# ArduinoInterface_v3_1.net
KiCad netlist of a schematic drawn in EAGLE
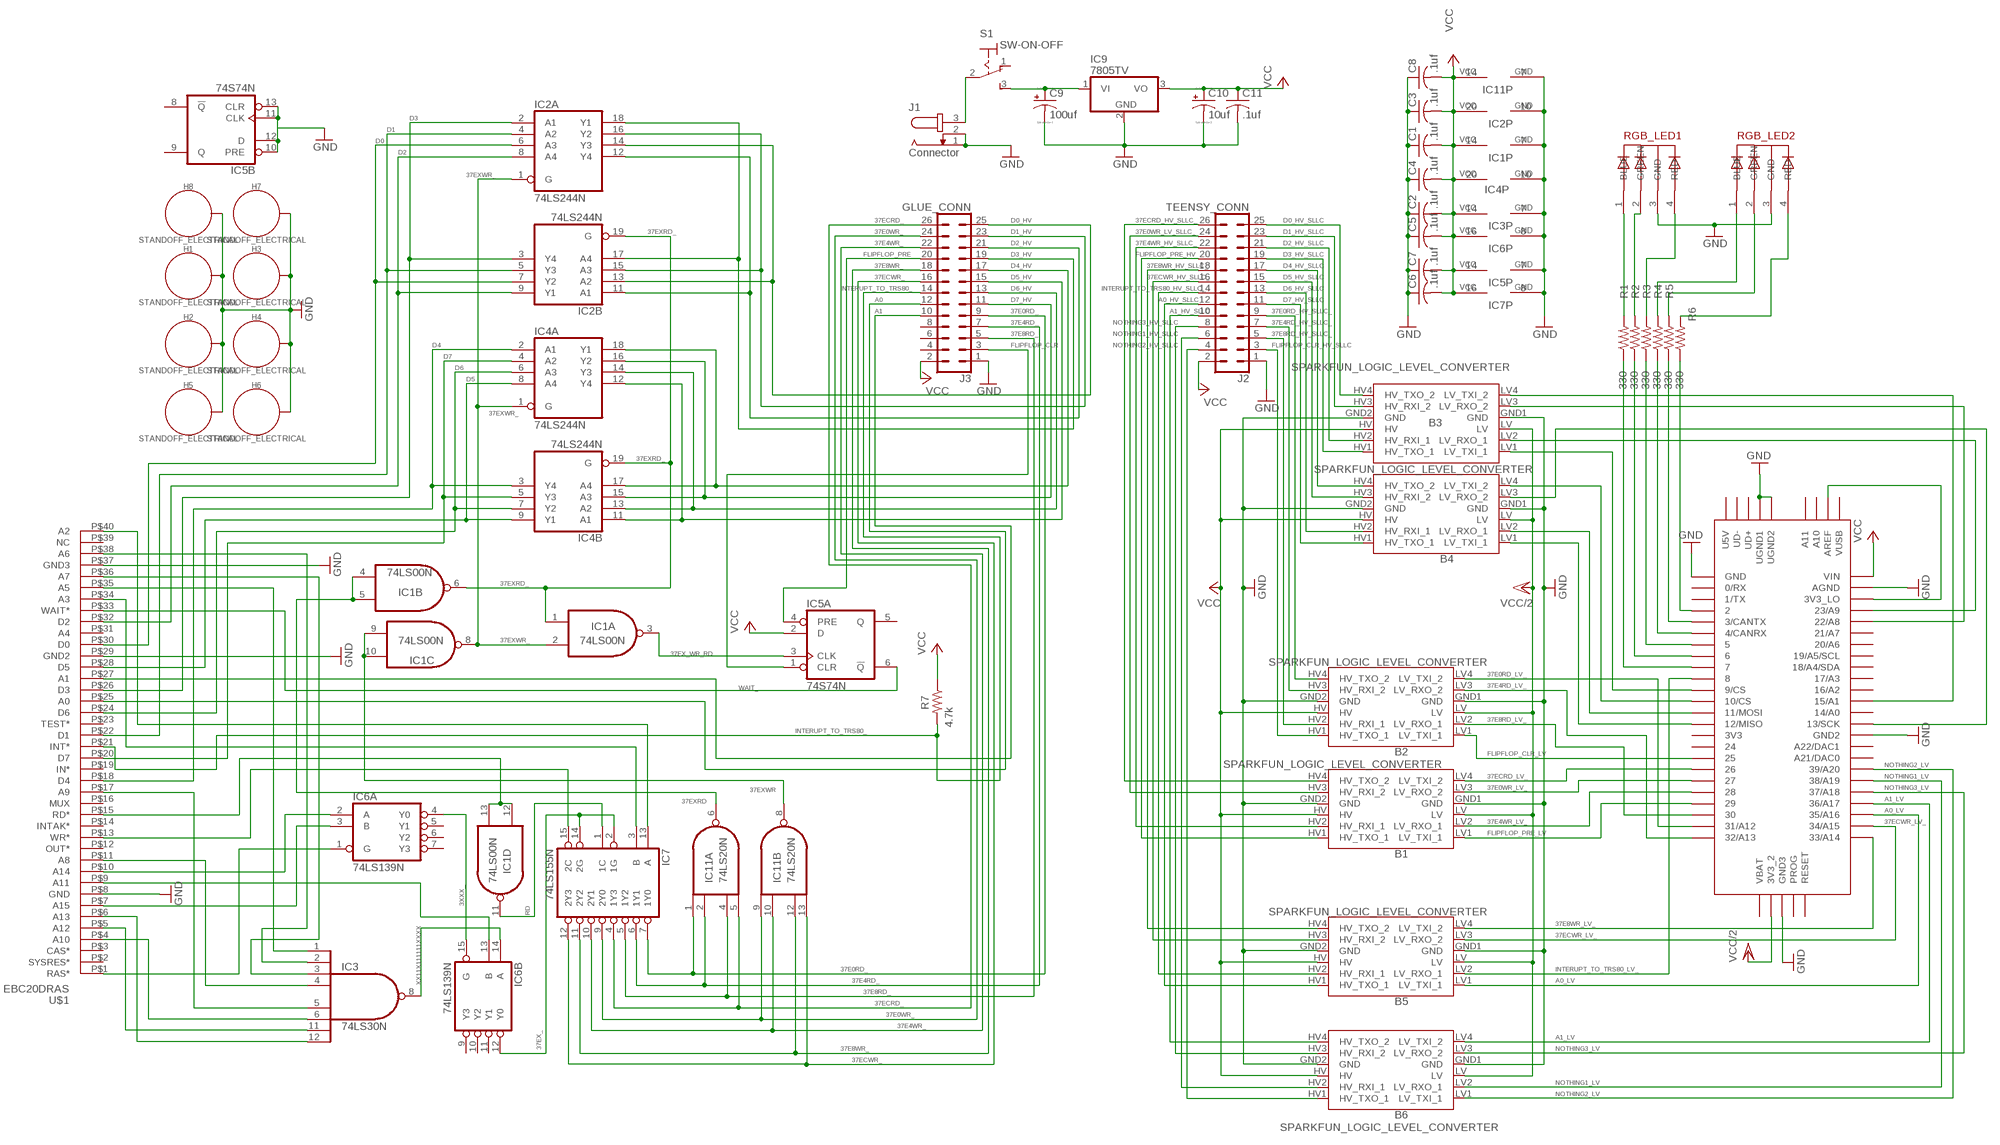
[diagram p0: schematic, sheet 1]

(export (version "E")
  (design (tool "Eeschema 10.0.6"))
  (components
    (comp (ref "B1")
      (value "SPARKFUN_LOGIC_LEVEL_CONVERTER")
      (footprint "eagle-import:SPARKFUN_LOGIC_LEVEL_CONVERTER")
      (libsource (lib "eagle-import") (part "SPARKFUN_LOGIC_LEVEL_CONVERTER"))
    )
    (comp (ref "B2")
      (value "SPARKFUN_LOGIC_LEVEL_CONVERTER")
      (footprint "eagle-import:SPARKFUN_LOGIC_LEVEL_CONVERTER")
      (libsource (lib "eagle-import") (part "SPARKFUN_LOGIC_LEVEL_CONVERTER"))
    )
    (comp (ref "B3")
      (value "SPARKFUN_LOGIC_LEVEL_CONVERTER")
      (footprint "eagle-import:SPARKFUN_LOGIC_LEVEL_CONVERTER")
      (libsource (lib "eagle-import") (part "SPARKFUN_LOGIC_LEVEL_CONVERTER"))
    )
    (comp (ref "B4")
      (value "SPARKFUN_LOGIC_LEVEL_CONVERTER")
      (footprint "eagle-import:SPARKFUN_LOGIC_LEVEL_CONVERTER")
      (libsource (lib "eagle-import") (part "SPARKFUN_LOGIC_LEVEL_CONVERTER"))
    )
    (comp (ref "B5")
      (value "SPARKFUN_LOGIC_LEVEL_CONVERTER")
      (footprint "eagle-import:SPARKFUN_LOGIC_LEVEL_CONVERTER")
      (libsource (lib "eagle-import") (part "SPARKFUN_LOGIC_LEVEL_CONVERTER"))
    )
    (comp (ref "B6")
      (value "SPARKFUN_LOGIC_LEVEL_CONVERTER")
      (footprint "eagle-import:SPARKFUN_LOGIC_LEVEL_CONVERTER")
      (libsource (lib "eagle-import") (part "SPARKFUN_LOGIC_LEVEL_CONVERTER"))
    )
    (comp (ref "C1")
      (value ".1uf")
      (footprint "eagle-import:C025-025X050")
      (libsource (lib "eagle-import") (part "C-US025-025X050"))
    )
    (comp (ref "C2")
      (value ".1uf")
      (footprint "eagle-import:C025-025X050")
      (libsource (lib "eagle-import") (part "C-US025-025X050"))
    )
    (comp (ref "C3")
      (value ".1uf")
      (footprint "eagle-import:C025-025X050")
      (libsource (lib "eagle-import") (part "C-US025-025X050"))
    )
    (comp (ref "C4")
      (value ".1uf")
      (footprint "eagle-import:C025-025X050")
      (libsource (lib "eagle-import") (part "C-US025-025X050"))
    )
    (comp (ref "C5")
      (value ".1uf")
      (footprint "eagle-import:C025-025X050")
      (libsource (lib "eagle-import") (part "C-US025-025X050"))
    )
    (comp (ref "C6")
      (value ".1uf")
      (footprint "eagle-import:C025-025X050")
      (libsource (lib "eagle-import") (part "C-US025-025X050"))
    )
    (comp (ref "C7")
      (value ".1uf")
      (footprint "eagle-import:C025-025X050")
      (libsource (lib "eagle-import") (part "C-US025-025X050"))
    )
    (comp (ref "C8")
      (value ".1uf")
      (footprint "eagle-import:C025-025X050")
      (libsource (lib "eagle-import") (part "C-US025-025X050"))
    )
    (comp (ref "C9")
      (value "100uf")
      (footprint "eagle-import:E5-6")
      (libsource (lib "eagle-import") (part "CPOL-USE5-6"))
    )
    (comp (ref "C10")
      (value "10uf")
      (footprint "eagle-import:E5-6")
      (libsource (lib "eagle-import") (part "CPOL-USE5-6"))
    )
    (comp (ref "C11")
      (value ".1uf")
      (footprint "eagle-import:C025-025X050")
      (libsource (lib "eagle-import") (part "C-US025-025X050"))
    )
    (comp (ref "H1")
      (value "STANDOFF_ELECTRICAL")
      (footprint "eagle-import:STANDOFF-ELECTRICAL")
      (libsource (lib "eagle-import") (part "STANDOFF_ELECTRICAL"))
    )
    (comp (ref "H2")
      (value "STANDOFF_ELECTRICAL")
      (footprint "eagle-import:STANDOFF-ELECTRICAL")
      (libsource (lib "eagle-import") (part "STANDOFF_ELECTRICAL"))
    )
    (comp (ref "H3")
      (value "STANDOFF_ELECTRICAL")
      (footprint "eagle-import:STANDOFF-ELECTRICAL")
      (libsource (lib "eagle-import") (part "STANDOFF_ELECTRICAL"))
    )
    (comp (ref "H4")
      (value "STANDOFF_ELECTRICAL")
      (footprint "eagle-import:STANDOFF-ELECTRICAL")
      (libsource (lib "eagle-import") (part "STANDOFF_ELECTRICAL"))
    )
    (comp (ref "H5")
      (value "STANDOFF_ELECTRICAL")
      (footprint "eagle-import:STANDOFF-ELECTRICAL")
      (libsource (lib "eagle-import") (part "STANDOFF_ELECTRICAL"))
    )
    (comp (ref "H6")
      (value "STANDOFF_ELECTRICAL")
      (footprint "eagle-import:STANDOFF-ELECTRICAL")
      (libsource (lib "eagle-import") (part "STANDOFF_ELECTRICAL"))
    )
    (comp (ref "H7")
      (value "STANDOFF_ELECTRICAL")
      (footprint "eagle-import:STANDOFF-ELECTRICAL")
      (libsource (lib "eagle-import") (part "STANDOFF_ELECTRICAL"))
    )
    (comp (ref "H8")
      (value "STANDOFF_ELECTRICAL")
      (footprint "eagle-import:STANDOFF-ELECTRICAL")
      (libsource (lib "eagle-import") (part "STANDOFF_ELECTRICAL"))
    )
    (comp (ref "IC1")
      (value "74LS00N")
      (footprint "eagle-import:DIL14")
      (libsource (lib "eagle-import") (part "7400NLS"))
    )
    (comp (ref "IC2")
      (value "74LS244N")
      (footprint "eagle-import:DIL20")
      (libsource (lib "eagle-import") (part "74244NLS"))
    )
    (comp (ref "IC3")
      (value "74LS30N")
      (footprint "eagle-import:DIL14")
      (libsource (lib "eagle-import") (part "7430NLS"))
    )
    (comp (ref "IC4")
      (value "74LS244N")
      (footprint "eagle-import:DIL20")
      (libsource (lib "eagle-import") (part "74244NLS"))
    )
    (comp (ref "IC5")
      (value "74S74N")
      (footprint "eagle-import:DIL14")
      (libsource (lib "eagle-import") (part "7474NS"))
    )
    (comp (ref "IC6")
      (value "74LS139N")
      (footprint "eagle-import:DIL16")
      (libsource (lib "eagle-import") (part "74139NLS"))
    )
    (comp (ref "IC7")
      (value "74LS155N")
      (footprint "eagle-import:DIL16")
      (libsource (lib "eagle-import") (part "74155NLS"))
    )
    (comp (ref "IC9")
      (value "7805TV")
      (footprint "eagle-import:TO220V")
      (libsource (lib "eagle-import") (part "78TV05"))
    )
    (comp (ref "IC11")
      (value "74LS20N")
      (footprint "eagle-import:DIL14")
      (libsource (lib "eagle-import") (part "7420NLS"))
    )
    (comp (ref "J1")
      (value "Connector")
      (footprint "eagle-import:SPC4077")
      (libsource (lib "eagle-import") (part "JACK-PLUG0"))
    )
    (comp (ref "J2")
      (value "TEENSY_CONN")
      (footprint "eagle-import:2X13")
      (libsource (lib "eagle-import") (part "CONN_13X22X13"))
    )
    (comp (ref "J3")
      (value "GLUE_CONN")
      (footprint "eagle-import:2X13")
      (libsource (lib "eagle-import") (part "CONN_13X22X13"))
    )
    (comp (ref "R1")
      (value "330")
      (footprint "eagle-import:0204V")
      (libsource (lib "eagle-import") (part "R-US_0204/2V"))
    )
    (comp (ref "R2")
      (value "330")
      (footprint "eagle-import:0204V")
      (libsource (lib "eagle-import") (part "R-US_0204/2V"))
    )
    (comp (ref "R3")
      (value "330")
      (footprint "eagle-import:0204V")
      (libsource (lib "eagle-import") (part "R-US_0204/2V"))
    )
    (comp (ref "R4")
      (value "330")
      (footprint "eagle-import:0204V")
      (libsource (lib "eagle-import") (part "R-US_0204/2V"))
    )
    (comp (ref "R5")
      (value "330")
      (footprint "eagle-import:0204V")
      (libsource (lib "eagle-import") (part "R-US_0204/2V"))
    )
    (comp (ref "R6")
      (value "330")
      (footprint "eagle-import:0204V")
      (libsource (lib "eagle-import") (part "R-US_0204/2V"))
    )
    (comp (ref "R7")
      (value "4.7k")
      (footprint "eagle-import:0204V")
      (libsource (lib "eagle-import") (part "R-US_0204/2V"))
    )
    (comp (ref "RGB_LED1")
      (value "5MMRGBLED")
      (footprint "eagle-import:LED5MMRGB")
      (libsource (lib "eagle-import") (part "5MMRGBLED"))
    )
    (comp (ref "RGB_LED2")
      (value "5MMRGBLED")
      (footprint "eagle-import:LED5MMRGB")
      (libsource (lib "eagle-import") (part "5MMRGBLED"))
    )
    (comp (ref "S1")
      (value "SW-ON-OFF")
      (footprint "eagle-import:M9040P")
      (libsource (lib "eagle-import") (part "M9040P"))
    )
    (comp (ref "U$1")
      (value "EBC20DRAS")
      (footprint "eagle-import:EBC20DRAS")
      (libsource (lib "eagle-import") (part "EBC20DRAS"))
    )
    (comp (ref "U$2")
      (value "TEENSY_3.5/3.6")
      (footprint "eagle-import:TEENSY_3.5_3.6")
      (libsource (lib "eagle-import") (part "TEENSY_3.5/3.6"))
    )
  )
  (nets
    (net (code "1") (name "/3XXX_") (class "Default")
      (node (ref "IC6") (pin "15") (pinfunction "G_15") (pintype "input"))
      (node (ref "IC6") (pin "4") (pinfunction "Y0_4") (pintype "output"))
    )
    (net (code "2") (name "/37E0RD_") (class "Default")
      (node (ref "IC11") (pin "1") (pinfunction "I0_1") (pintype "input"))
      (node (ref "IC7") (pin "7") (pinfunction "1Y0_7") (pintype "output"))
      (node (ref "J3") (pin "9") (pinfunction "9_9") (pintype "passive"))
    )
    (net (code "3") (name "/37E0RD_HV_SLLC_") (class "Default")
      (node (ref "B2") (pin "HV4") (pinfunction "HV_TXO_2_HV4") (pintype "bidirectional"))
      (node (ref "J2") (pin "9") (pinfunction "9_9") (pintype "passive"))
    )
    (net (code "4") (name "/37E0RD_LV_") (class "Default")
      (node (ref "B2") (pin "LV4") (pinfunction "LV_TXI_2_LV4") (pintype "bidirectional"))
      (node (ref "U$2") (pin "31/A12") (pinfunction "31/A12_31/A12") (pintype "bidirectional"))
    )
    (net (code "5") (name "/37E0WR_") (class "Default")
      (node (ref "IC11") (pin "9") (pinfunction "I0_9") (pintype "input"))
      (node (ref "IC7") (pin "9") (pinfunction "2Y0_9") (pintype "output"))
      (node (ref "J3") (pin "24") (pinfunction "24_24") (pintype "passive"))
    )
    (net (code "6") (name "/37E0WR_LV_") (class "Default")
      (node (ref "B1") (pin "LV3") (pinfunction "LV_RXO_2_LV3") (pintype "bidirectional"))
      (node (ref "U$2") (pin "27") (pinfunction "27_27") (pintype "bidirectional"))
    )
    (net (code "7") (name "/37E0WR_LV_SLLC_") (class "Default")
      (node (ref "B1") (pin "HV3") (pinfunction "HV_RXI_2_HV3") (pintype "bidirectional"))
      (node (ref "J2") (pin "24") (pinfunction "24_24") (pintype "passive"))
    )
    (net (code "8") (name "/37E4RD_") (class "Default")
      (node (ref "IC11") (pin "2") (pinfunction "I1_2") (pintype "input"))
      (node (ref "IC7") (pin "6") (pinfunction "1Y1_6") (pintype "output"))
      (node (ref "J3") (pin "7") (pinfunction "7_7") (pintype "passive"))
    )
    (net (code "9") (name "/37E4RD_HV_SLLC_") (class "Default")
      (node (ref "B2") (pin "HV3") (pinfunction "HV_RXI_2_HV3") (pintype "bidirectional"))
      (node (ref "J2") (pin "7") (pinfunction "7_7") (pintype "passive"))
    )
    (net (code "10") (name "/37E4RD_LV_") (class "Default")
      (node (ref "B2") (pin "LV3") (pinfunction "LV_RXO_2_LV3") (pintype "bidirectional"))
      (node (ref "U$2") (pin "32/A13") (pinfunction "32/A13_32/A13") (pintype "bidirectional"))
    )
    (net (code "11") (name "/37E4WR_") (class "Default")
      (node (ref "IC11") (pin "10") (pinfunction "I1_10") (pintype "input"))
      (node (ref "IC7") (pin "10") (pinfunction "2Y1_10") (pintype "output"))
      (node (ref "J3") (pin "22") (pinfunction "22_22") (pintype "passive"))
    )
    (net (code "12") (name "/37E4WR_HV_SLLC_") (class "Default")
      (node (ref "B1") (pin "HV2") (pinfunction "HV_RXI_1_HV2") (pintype "bidirectional"))
      (node (ref "J2") (pin "22") (pinfunction "22_22") (pintype "passive"))
    )
    (net (code "13") (name "/37E4WR_LV_") (class "Default")
      (node (ref "B1") (pin "LV2") (pinfunction "LV_RXO_1_LV2") (pintype "bidirectional"))
      (node (ref "U$2") (pin "28") (pinfunction "28_28") (pintype "bidirectional"))
    )
    (net (code "14") (name "/37E8RD_") (class "Default")
      (node (ref "IC11") (pin "4") (pinfunction "I2_4") (pintype "input"))
      (node (ref "IC7") (pin "5") (pinfunction "1Y2_5") (pintype "output"))
      (node (ref "J3") (pin "5") (pinfunction "5_5") (pintype "passive"))
    )
    (net (code "15") (name "/37E8RD_HV_SLLC_") (class "Default")
      (node (ref "B2") (pin "HV2") (pinfunction "HV_RXI_1_HV2") (pintype "bidirectional"))
      (node (ref "J2") (pin "5") (pinfunction "5_5") (pintype "passive"))
    )
    (net (code "16") (name "/37E8RD_LV_") (class "Default")
      (node (ref "B2") (pin "LV2") (pinfunction "LV_RXO_1_LV2") (pintype "bidirectional"))
      (node (ref "U$2") (pin "30") (pinfunction "30_30") (pintype "bidirectional"))
    )
    (net (code "17") (name "/37E8WR_") (class "Default")
      (node (ref "IC11") (pin "12") (pinfunction "I2_12") (pintype "input"))
      (node (ref "IC7") (pin "11") (pinfunction "2Y2_11") (pintype "output"))
      (node (ref "J3") (pin "18") (pinfunction "18_18") (pintype "passive"))
    )
    (net (code "18") (name "/37E8WR_HV_SLLC_") (class "Default")
      (node (ref "B5") (pin "HV4") (pinfunction "HV_TXO_2_HV4") (pintype "bidirectional"))
      (node (ref "J2") (pin "18") (pinfunction "18_18") (pintype "passive"))
    )
    (net (code "19") (name "/37E8WR_LV_") (class "Default")
      (node (ref "B5") (pin "LV4") (pinfunction "LV_TXI_2_LV4") (pintype "bidirectional"))
      (node (ref "U$2") (pin "33/A14") (pinfunction "33/A14_33/A14") (pintype "bidirectional"))
    )
    (net (code "20") (name "/37ECRD_") (class "Default")
      (node (ref "IC11") (pin "5") (pinfunction "I3_5") (pintype "input"))
      (node (ref "IC7") (pin "4") (pinfunction "1Y3_4") (pintype "output"))
      (node (ref "J3") (pin "26") (pinfunction "26_26") (pintype "passive"))
    )
    (net (code "21") (name "/37ECRD_HV_SLLC_") (class "Default")
      (node (ref "B1") (pin "HV4") (pinfunction "HV_TXO_2_HV4") (pintype "bidirectional"))
      (node (ref "J2") (pin "26") (pinfunction "26_26") (pintype "passive"))
    )
    (net (code "22") (name "/37ECRD_LV_") (class "Default")
      (node (ref "B1") (pin "LV4") (pinfunction "LV_TXI_2_LV4") (pintype "bidirectional"))
      (node (ref "U$2") (pin "26") (pinfunction "26_26") (pintype "bidirectional"))
    )
    (net (code "23") (name "/37ECWR_") (class "Default")
      (node (ref "IC11") (pin "13") (pinfunction "I3_13") (pintype "input"))
      (node (ref "IC7") (pin "12") (pinfunction "2Y3_12") (pintype "output"))
      (node (ref "J3") (pin "16") (pinfunction "16_16") (pintype "passive"))
    )
    (net (code "24") (name "/37ECWR_HV_SLLC_") (class "Default")
      (node (ref "B5") (pin "HV3") (pinfunction "HV_RXI_2_HV3") (pintype "bidirectional"))
      (node (ref "J2") (pin "16") (pinfunction "16_16") (pintype "passive"))
    )
    (net (code "25") (name "/37ECWR_LV_") (class "Default")
      (node (ref "B5") (pin "LV3") (pinfunction "LV_RXO_2_LV3") (pintype "bidirectional"))
      (node (ref "U$2") (pin "34/A15") (pinfunction "34/A15_34/A15") (pintype "bidirectional"))
    )
    (net (code "26") (name "/37EXRD") (class "Default")
      (node (ref "IC1") (pin "4") (pinfunction "I0_4") (pintype "input"))
      (node (ref "IC1") (pin "5") (pinfunction "I1_5") (pintype "input"))
      (node (ref "IC11") (pin "6") (pinfunction "O_6") (pintype "output"))
    )
    (net (code "27") (name "/37EXRD_") (class "Default")
      (node (ref "IC1") (pin "1") (pinfunction "I0_1") (pintype "input"))
      (node (ref "IC1") (pin "6") (pinfunction "O_6") (pintype "output"))
      (node (ref "IC2") (pin "19") (pinfunction "G_19") (pintype "input"))
      (node (ref "IC4") (pin "19") (pinfunction "G_19") (pintype "input"))
    )
    (net (code "28") (name "/37EXWR") (class "Default")
      (node (ref "IC1") (pin "10") (pinfunction "I1_10") (pintype "input"))
      (node (ref "IC1") (pin "9") (pinfunction "I0_9") (pintype "input"))
      (node (ref "IC11") (pin "8") (pinfunction "O_8") (pintype "output"))
    )
    (net (code "29") (name "/37EXWR_") (class "Default")
      (node (ref "IC1") (pin "2") (pinfunction "I1_2") (pintype "input"))
      (node (ref "IC1") (pin "8") (pinfunction "O_8") (pintype "output"))
      (node (ref "IC2") (pin "1") (pinfunction "G_1") (pintype "input"))
      (node (ref "IC4") (pin "1") (pinfunction "G_1") (pintype "input"))
    )
    (net (code "30") (name "/37EX_") (class "Default")
      (node (ref "IC6") (pin "12") (pinfunction "Y0_12") (pintype "output"))
      (node (ref "IC7") (pin "14") (pinfunction "2G_14") (pintype "input"))
      (node (ref "IC7") (pin "2") (pinfunction "1G_2") (pintype "input"))
    )
    (net (code "31") (name "/37EX_WR_RD") (class "Default")
      (node (ref "IC1") (pin "3") (pinfunction "O_3") (pintype "output"))
      (node (ref "IC5") (pin "3") (pinfunction "CLK_3") (pintype "input"))
    )
    (net (code "32") (name "/A0") (class "Default")
      (node (ref "J3") (pin "12") (pinfunction "12_12") (pintype "passive"))
      (node (ref "U$1") (pin "P$25") (pinfunction "A0_P$25") (pintype "bidirectional"))
    )
    (net (code "33") (name "/A0_HV_SLLC") (class "Default")
      (node (ref "B5") (pin "HV1") (pinfunction "HV_TXO_1_HV1") (pintype "bidirectional"))
      (node (ref "J2") (pin "12") (pinfunction "12_12") (pintype "passive"))
    )
    (net (code "34") (name "/A0_LV") (class "Default")
      (node (ref "B5") (pin "LV1") (pinfunction "LV_TXI_1_LV1") (pintype "bidirectional"))
      (node (ref "U$2") (pin "35/A16") (pinfunction "35/A16_35/A16") (pintype "bidirectional"))
    )
    (net (code "35") (name "/A1") (class "Default")
      (node (ref "J3") (pin "10") (pinfunction "10_10") (pintype "passive"))
      (node (ref "U$1") (pin "P$27") (pinfunction "A1_P$27") (pintype "bidirectional"))
    )
    (net (code "36") (name "/A1_HV_SLLC") (class "Default")
      (node (ref "B6") (pin "HV4") (pinfunction "HV_TXO_2_HV4") (pintype "bidirectional"))
      (node (ref "J2") (pin "10") (pinfunction "10_10") (pintype "passive"))
    )
    (net (code "37") (name "/A1_LV") (class "Default")
      (node (ref "B6") (pin "LV4") (pinfunction "LV_TXI_2_LV4") (pintype "bidirectional"))
      (node (ref "U$2") (pin "36/A17") (pinfunction "36/A17_36/A17") (pintype "bidirectional"))
    )
    (net (code "38") (name "/D0") (class "Default")
      (node (ref "IC2") (pin "6") (pinfunction "A3_6") (pintype "input"))
      (node (ref "IC2") (pin "7") (pinfunction "Y2_7") (pintype "tri_state"))
      (node (ref "U$1") (pin "P$30") (pinfunction "D0_P$30") (pintype "bidirectional"))
    )
    (net (code "39") (name "/D0_HV") (class "Default")
      (node (ref "IC2") (pin "13") (pinfunction "A2_13") (pintype "input"))
      (node (ref "IC2") (pin "14") (pinfunction "Y3_14") (pintype "tri_state"))
      (node (ref "J3") (pin "25") (pinfunction "25_25") (pintype "passive"))
    )
    (net (code "40") (name "/D0_HV_SLLC") (class "Default")
      (node (ref "B3") (pin "HV4") (pinfunction "HV_TXO_2_HV4") (pintype "bidirectional"))
      (node (ref "J2") (pin "25") (pinfunction "25_25") (pintype "passive"))
    )
    (net (code "41") (name "/D1") (class "Default")
      (node (ref "IC2") (pin "4") (pinfunction "A2_4") (pintype "input"))
      (node (ref "IC2") (pin "5") (pinfunction "Y3_5") (pintype "tri_state"))
      (node (ref "U$1") (pin "P$22") (pinfunction "D1_P$22") (pintype "bidirectional"))
    )
    (net (code "42") (name "/D1_HV") (class "Default")
      (node (ref "IC2") (pin "15") (pinfunction "A3_15") (pintype "input"))
      (node (ref "IC2") (pin "16") (pinfunction "Y2_16") (pintype "tri_state"))
      (node (ref "J3") (pin "23") (pinfunction "23_23") (pintype "passive"))
    )
    (net (code "43") (name "/D1_HV_SLLC") (class "Default")
      (node (ref "B3") (pin "HV3") (pinfunction "HV_RXI_2_HV3") (pintype "bidirectional"))
      (node (ref "J2") (pin "23") (pinfunction "23_23") (pintype "passive"))
    )
    (net (code "44") (name "/D2") (class "Default")
      (node (ref "IC2") (pin "8") (pinfunction "A4_8") (pintype "input"))
      (node (ref "IC2") (pin "9") (pinfunction "Y1_9") (pintype "tri_state"))
      (node (ref "U$1") (pin "P$32") (pinfunction "D2_P$32") (pintype "bidirectional"))
    )
    (net (code "45") (name "/D2_HV") (class "Default")
      (node (ref "IC2") (pin "11") (pinfunction "A1_11") (pintype "input"))
      (node (ref "IC2") (pin "12") (pinfunction "Y4_12") (pintype "tri_state"))
      (node (ref "J3") (pin "21") (pinfunction "21_21") (pintype "passive"))
    )
    (net (code "46") (name "/D2_HV_SLLC") (class "Default")
      (node (ref "B3") (pin "HV2") (pinfunction "HV_RXI_1_HV2") (pintype "bidirectional"))
      (node (ref "J2") (pin "21") (pinfunction "21_21") (pintype "passive"))
    )
    (net (code "47") (name "/D3") (class "Default")
      (node (ref "IC2") (pin "2") (pinfunction "A1_2") (pintype "input"))
      (node (ref "IC2") (pin "3") (pinfunction "Y4_3") (pintype "tri_state"))
      (node (ref "U$1") (pin "P$26") (pinfunction "D3_P$26") (pintype "bidirectional"))
    )
    (net (code "48") (name "/D3_HV") (class "Default")
      (node (ref "IC2") (pin "17") (pinfunction "A4_17") (pintype "input"))
      (node (ref "IC2") (pin "18") (pinfunction "Y1_18") (pintype "tri_state"))
      (node (ref "J3") (pin "19") (pinfunction "19_19") (pintype "passive"))
    )
    (net (code "49") (name "/D3_HV_SLLC") (class "Default")
      (node (ref "B3") (pin "HV1") (pinfunction "HV_TXO_1_HV1") (pintype "bidirectional"))
      (node (ref "J2") (pin "19") (pinfunction "19_19") (pintype "passive"))
    )
    (net (code "50") (name "/D4") (class "Default")
      (node (ref "IC4") (pin "2") (pinfunction "A1_2") (pintype "input"))
      (node (ref "IC4") (pin "3") (pinfunction "Y4_3") (pintype "tri_state"))
      (node (ref "U$1") (pin "P$18") (pinfunction "D4_P$18") (pintype "bidirectional"))
    )
    (net (code "51") (name "/D4_HV") (class "Default")
      (node (ref "IC4") (pin "17") (pinfunction "A4_17") (pintype "input"))
      (node (ref "IC4") (pin "18") (pinfunction "Y1_18") (pintype "tri_state"))
      (node (ref "J3") (pin "17") (pinfunction "17_17") (pintype "passive"))
    )
    (net (code "52") (name "/D4_HV_SLLC") (class "Default")
      (node (ref "B4") (pin "HV4") (pinfunction "HV_TXO_2_HV4") (pintype "bidirectional"))
      (node (ref "J2") (pin "17") (pinfunction "17_17") (pintype "passive"))
    )
    (net (code "53") (name "/D5") (class "Default")
      (node (ref "IC4") (pin "8") (pinfunction "A4_8") (pintype "input"))
      (node (ref "IC4") (pin "9") (pinfunction "Y1_9") (pintype "tri_state"))
      (node (ref "U$1") (pin "P$28") (pinfunction "D5_P$28") (pintype "bidirectional"))
    )
    (net (code "54") (name "/D5_HV") (class "Default")
      (node (ref "IC4") (pin "11") (pinfunction "A1_11") (pintype "input"))
      (node (ref "IC4") (pin "12") (pinfunction "Y4_12") (pintype "tri_state"))
      (node (ref "J3") (pin "15") (pinfunction "15_15") (pintype "passive"))
    )
    (net (code "55") (name "/D5_HV_SLLC") (class "Default")
      (node (ref "B4") (pin "HV3") (pinfunction "HV_RXI_2_HV3") (pintype "bidirectional"))
      (node (ref "J2") (pin "15") (pinfunction "15_15") (pintype "passive"))
    )
    (net (code "56") (name "/D6") (class "Default")
      (node (ref "IC4") (pin "6") (pinfunction "A3_6") (pintype "input"))
      (node (ref "IC4") (pin "7") (pinfunction "Y2_7") (pintype "tri_state"))
      (node (ref "U$1") (pin "P$24") (pinfunction "D6_P$24") (pintype "bidirectional"))
    )
    (net (code "57") (name "/D6_HV") (class "Default")
      (node (ref "IC4") (pin "13") (pinfunction "A2_13") (pintype "input"))
      (node (ref "IC4") (pin "14") (pinfunction "Y3_14") (pintype "tri_state"))
      (node (ref "J3") (pin "13") (pinfunction "13_13") (pintype "passive"))
    )
    (net (code "58") (name "/D6_HV_SLLC") (class "Default")
      (node (ref "B4") (pin "HV2") (pinfunction "HV_RXI_1_HV2") (pintype "bidirectional"))
      (node (ref "J2") (pin "13") (pinfunction "13_13") (pintype "passive"))
    )
    (net (code "59") (name "/D7") (class "Default")
      (node (ref "IC4") (pin "4") (pinfunction "A2_4") (pintype "input"))
      (node (ref "IC4") (pin "5") (pinfunction "Y3_5") (pintype "tri_state"))
      (node (ref "U$1") (pin "P$20") (pinfunction "D7_P$20") (pintype "bidirectional"))
    )
    (net (code "60") (name "/D7_HV") (class "Default")
      (node (ref "IC4") (pin "15") (pinfunction "A3_15") (pintype "input"))
      (node (ref "IC4") (pin "16") (pinfunction "Y2_16") (pintype "tri_state"))
      (node (ref "J3") (pin "11") (pinfunction "11_11") (pintype "passive"))
    )
    (net (code "61") (name "/D7_HV_SLLC") (class "Default")
      (node (ref "B4") (pin "HV1") (pinfunction "HV_TXO_1_HV1") (pintype "bidirectional"))
      (node (ref "J2") (pin "11") (pinfunction "11_11") (pintype "passive"))
    )
    (net (code "62") (name "/FLIPFLOP_CLR") (class "Default")
      (node (ref "IC5") (pin "1") (pinfunction "CLR_1") (pintype "input"))
      (node (ref "J3") (pin "3") (pinfunction "3_3") (pintype "passive"))
    )
    (net (code "63") (name "/FLIPFLOP_CLR_HV_SLLC") (class "Default")
      (node (ref "B2") (pin "HV1") (pinfunction "HV_TXO_1_HV1") (pintype "bidirectional"))
      (node (ref "J2") (pin "3") (pinfunction "3_3") (pintype "passive"))
    )
    (net (code "64") (name "/FLIPFLOP_CLR_LV") (class "Default")
      (node (ref "B2") (pin "LV1") (pinfunction "LV_TXI_1_LV1") (pintype "bidirectional"))
      (node (ref "U$2") (pin "25") (pinfunction "25_25") (pintype "bidirectional"))
    )
    (net (code "65") (name "/FLIPFLOP_PRE") (class "Default")
      (node (ref "IC5") (pin "4") (pinfunction "PRE_4") (pintype "input"))
      (node (ref "J3") (pin "20") (pinfunction "20_20") (pintype "passive"))
    )
    (net (code "66") (name "/FLIPFLOP_PRE_HV") (class "Default")
      (node (ref "B1") (pin "HV1") (pinfunction "HV_TXO_1_HV1") (pintype "bidirectional"))
      (node (ref "J2") (pin "20") (pinfunction "20_20") (pintype "passive"))
    )
    (net (code "67") (name "/FLIPFLOP_PRE_LV") (class "Default")
      (node (ref "B1") (pin "LV1") (pinfunction "LV_TXI_1_LV1") (pintype "bidirectional"))
      (node (ref "U$2") (pin "29") (pinfunction "29_29") (pintype "bidirectional"))
    )
    (net (code "68") (name "/INTERUPT_TO_TRS80_") (class "Default")
      (node (ref "J3") (pin "14") (pinfunction "14_14") (pintype "passive"))
      (node (ref "R7") (pin "2") (pinfunction "2_2") (pintype "passive"))
      (node (ref "U$1") (pin "P$21") (pinfunction "INT*_P$21") (pintype "bidirectional"))
    )
    (net (code "69") (name "/INTERUPT_TO_TRS80_HV_SLLC_") (class "Default")
      (node (ref "B5") (pin "HV2") (pinfunction "HV_RXI_1_HV2") (pintype "bidirectional"))
      (node (ref "J2") (pin "14") (pinfunction "14_14") (pintype "passive"))
    )
    (net (code "70") (name "/INTERUPT_TO_TRS80_LV_") (class "Default")
      (node (ref "B5") (pin "LV2") (pinfunction "LV_RXO_1_LV2") (pintype "bidirectional"))
      (node (ref "U$2") (pin "8") (pinfunction "8_8") (pintype "bidirectional"))
    )
    (net (code "71") (name "/NOTHING1_HV_SLLC") (class "Default")
      (node (ref "B6") (pin "HV2") (pinfunction "HV_RXI_1_HV2") (pintype "bidirectional"))
      (node (ref "J2") (pin "6") (pinfunction "6_6") (pintype "passive"))
    )
    (net (code "72") (name "/NOTHING1_LV") (class "Default")
      (node (ref "B6") (pin "LV2") (pinfunction "LV_RXO_1_LV2") (pintype "bidirectional"))
      (node (ref "U$2") (pin "38/A19") (pinfunction "38/A19_38/A19") (pintype "bidirectional"))
    )
    (net (code "73") (name "/NOTHING2_HV_SLLC") (class "Default")
      (node (ref "B6") (pin "HV1") (pinfunction "HV_TXO_1_HV1") (pintype "bidirectional"))
      (node (ref "J2") (pin "4") (pinfunction "4_4") (pintype "passive"))
    )
    (net (code "74") (name "/NOTHING2_LV") (class "Default")
      (node (ref "B6") (pin "LV1") (pinfunction "LV_TXI_1_LV1") (pintype "bidirectional"))
      (node (ref "U$2") (pin "39/A20") (pinfunction "39/A20_39/A20") (pintype "bidirectional"))
    )
    (net (code "75") (name "/NOTHING3_HV_SLLC") (class "Default")
      (node (ref "B6") (pin "HV3") (pinfunction "HV_RXI_2_HV3") (pintype "bidirectional"))
      (node (ref "J2") (pin "8") (pinfunction "8_8") (pintype "passive"))
    )
    (net (code "76") (name "/NOTHING3_LV") (class "Default")
      (node (ref "B6") (pin "LV3") (pinfunction "LV_RXO_2_LV3") (pintype "bidirectional"))
      (node (ref "U$2") (pin "37/A18") (pinfunction "37/A18_37/A18") (pintype "bidirectional"))
    )
    (net (code "77") (name "/RD") (class "Default")
      (node (ref "IC1") (pin "11") (pinfunction "O_11") (pintype "output"))
      (node (ref "IC7") (pin "1") (pinfunction "1C_1") (pintype "input"))
    )
    (net (code "78") (name "/WAIT_") (class "Default")
      (node (ref "IC5") (pin "6") (pinfunction "~{Q}_6") (pintype "output"))
      (node (ref "U$1") (pin "P$33") (pinfunction "WAIT*_P$33") (pintype "bidirectional"))
    )
    (net (code "79") (name "/XX11X111111XXXX") (class "Default")
      (node (ref "IC3") (pin "8") (pinfunction "O_8") (pintype "output"))
      (node (ref "IC6") (pin "14") (pinfunction "A_14") (pintype "input"))
    )
    (net (code "80") (name "GND") (class "Default")
      (node (ref "B1") (pin "GND1") (pinfunction "GND_GND1") (pintype "power_in"))
      (node (ref "B1") (pin "GND2") (pinfunction "GND_GND2") (pintype "power_in"))
      (node (ref "B2") (pin "GND1") (pinfunction "GND_GND1") (pintype "power_in"))
      (node (ref "B2") (pin "GND2") (pinfunction "GND_GND2") (pintype "power_in"))
      (node (ref "B3") (pin "GND1") (pinfunction "GND_GND1") (pintype "power_in"))
      (node (ref "B3") (pin "GND2") (pinfunction "GND_GND2") (pintype "power_in"))
      (node (ref "B4") (pin "GND1") (pinfunction "GND_GND1") (pintype "power_in"))
      (node (ref "B4") (pin "GND2") (pinfunction "GND_GND2") (pintype "power_in"))
      (node (ref "B5") (pin "GND1") (pinfunction "GND_GND1") (pintype "power_in"))
      (node (ref "B5") (pin "GND2") (pinfunction "GND_GND2") (pintype "power_in"))
      (node (ref "B6") (pin "GND1") (pinfunction "GND_GND1") (pintype "power_in"))
      (node (ref "B6") (pin "GND2") (pinfunction "GND_GND2") (pintype "power_in"))
      (node (ref "C1") (pin "1") (pinfunction "1_1") (pintype "passive"))
      (node (ref "C10") (pin "-") (pinfunction "-_-") (pintype "passive"))
      (node (ref "C11") (pin "2") (pinfunction "2_2") (pintype "passive"))
      (node (ref "C2") (pin "1") (pinfunction "1_1") (pintype "passive"))
      (node (ref "C3") (pin "1") (pinfunction "1_1") (pintype "passive"))
      (node (ref "C4") (pin "1") (pinfunction "1_1") (pintype "passive"))
      (node (ref "C5") (pin "1") (pinfunction "1_1") (pintype "passive"))
      (node (ref "C6") (pin "1") (pinfunction "1_1") (pintype "passive"))
      (node (ref "C7") (pin "1") (pinfunction "1_1") (pintype "passive"))
      (node (ref "C8") (pin "1") (pinfunction "1_1") (pintype "passive"))
      (node (ref "C9") (pin "-") (pinfunction "-_-") (pintype "passive"))
      (node (ref "H1") (pin "P1") (pinfunction "P$1_P1") (pintype "bidirectional"))
      (node (ref "H2") (pin "P1") (pinfunction "P$1_P1") (pintype "bidirectional"))
      (node (ref "H3") (pin "P1") (pinfunction "P$1_P1") (pintype "bidirectional"))
      (node (ref "H4") (pin "P1") (pinfunction "P$1_P1") (pintype "bidirectional"))
      (node (ref "H5") (pin "P1") (pinfunction "P$1_P1") (pintype "bidirectional"))
      (node (ref "H6") (pin "P1") (pinfunction "P$1_P1") (pintype "bidirectional"))
      (node (ref "H7") (pin "P1") (pinfunction "P$1_P1") (pintype "bidirectional"))
      (node (ref "H8") (pin "P1") (pinfunction "P$1_P1") (pintype "bidirectional"))
      (node (ref "IC1") (pin "7") (pinfunction "GND_7") (pintype "power_in"))
      (node (ref "IC11") (pin "7") (pinfunction "GND_7") (pintype "power_in"))
      (node (ref "IC2") (pin "10") (pinfunction "GND_10") (pintype "power_in"))
      (node (ref "IC3") (pin "7") (pinfunction "GND_7") (pintype "power_in"))
      (node (ref "IC4") (pin "10") (pinfunction "GND_10") (pintype "power_in"))
      (node (ref "IC5") (pin "10") (pinfunction "PRE_10") (pintype "input"))
      (node (ref "IC5") (pin "11") (pinfunction "CLK_11") (pintype "input"))
      (node (ref "IC5") (pin "12") (pinfunction "D_12") (pintype "input"))
      (node (ref "IC5") (pin "13") (pinfunction "CLR_13") (pintype "input"))
      (node (ref "IC5") (pin "7") (pinfunction "GND_7") (pintype "power_in"))
      (node (ref "IC6") (pin "8") (pinfunction "GND_8") (pintype "power_in"))
      (node (ref "IC7") (pin "8") (pinfunction "GND_8") (pintype "power_in"))
      (node (ref "IC9") (pin "2") (pinfunction "GND_2") (pintype "passive"))
      (node (ref "J1") (pin "1") (pinfunction "1_1") (pintype "passive"))
      (node (ref "J1") (pin "2") (pinfunction "2_2") (pintype "passive"))
      (node (ref "J2") (pin "1") (pinfunction "1_1") (pintype "passive"))
      (node (ref "J3") (pin "1") (pinfunction "1_1") (pintype "passive"))
      (node (ref "RGB_LED1") (pin "3") (pinfunction "GND_3") (pintype "bidirectional"))
      (node (ref "RGB_LED2") (pin "3") (pinfunction "GND_3") (pintype "bidirectional"))
      (node (ref "U$1") (pin "P$29") (pinfunction "GND2_P$29") (pintype "bidirectional"))
      (node (ref "U$1") (pin "P$37") (pinfunction "GND3_P$37") (pintype "bidirectional"))
      (node (ref "U$1") (pin "P$8") (pinfunction "GND_P$8") (pintype "bidirectional"))
      (node (ref "U$2") (pin "AGND") (pinfunction "AGND_AGND") (pintype "bidirectional"))
      (node (ref "U$2") (pin "GND") (pinfunction "GND_GND") (pintype "bidirectional"))
      (node (ref "U$2") (pin "GND2") (pinfunction "GND2_GND2") (pintype "bidirectional"))
      (node (ref "U$2") (pin "GND3") (pinfunction "GND3_GND3") (pintype "bidirectional"))
      (node (ref "U$2") (pin "UGND1") (pinfunction "UGND1_UGND1") (pintype "bidirectional"))
      (node (ref "U$2") (pin "UGND2") (pinfunction "UGND2_UGND2") (pintype "bidirectional"))
    )
    (net (code "81") (name "Net-(B3-LV_RXO_1)") (class "Default")
      (node (ref "B3") (pin "LV2") (pinfunction "LV_RXO_1_LV2") (pintype "bidirectional"))
      (node (ref "U$2") (pin "23/A9") (pinfunction "23/A9_23/A9") (pintype "bidirectional"))
    )
    (net (code "82") (name "Net-(B3-LV_RXO_2)") (class "Default")
      (node (ref "B3") (pin "LV3") (pinfunction "LV_RXO_2_LV3") (pintype "bidirectional"))
      (node (ref "U$2") (pin "22/A8") (pinfunction "22/A8_22/A8") (pintype "bidirectional"))
    )
    (net (code "83") (name "Net-(B3-LV_TXI_1)") (class "Default")
      (node (ref "B3") (pin "LV1") (pinfunction "LV_TXI_1_LV1") (pintype "bidirectional"))
      (node (ref "U$2") (pin "9/CS") (pinfunction "9/CS_9/CS") (pintype "bidirectional"))
    )
    (net (code "84") (name "Net-(B3-LV_TXI_2)") (class "Default")
      (node (ref "B3") (pin "LV4") (pinfunction "LV_TXI_2_LV4") (pintype "bidirectional"))
      (node (ref "U$2") (pin "15/A1") (pinfunction "15/A1_15/A1") (pintype "bidirectional"))
    )
    (net (code "85") (name "Net-(B4-LV_RXO_1)") (class "Default")
      (node (ref "B4") (pin "LV2") (pinfunction "LV_RXO_1_LV2") (pintype "bidirectional"))
      (node (ref "U$2") (pin "11/MOSI") (pinfunction "11/MOSI_11/MOSI") (pintype "bidirectional"))
    )
    (net (code "86") (name "Net-(B4-LV_RXO_2)") (class "Default")
      (node (ref "B4") (pin "LV3") (pinfunction "LV_RXO_2_LV3") (pintype "bidirectional"))
      (node (ref "U$2") (pin "13/SCK") (pinfunction "13/SCK_13/SCK") (pintype "bidirectional"))
    )
    (net (code "87") (name "Net-(B4-LV_TXI_1)") (class "Default")
      (node (ref "B4") (pin "LV1") (pinfunction "LV_TXI_1_LV1") (pintype "bidirectional"))
      (node (ref "U$2") (pin "12/MISO") (pinfunction "12/MISO_12/MISO") (pintype "bidirectional"))
    )
    (net (code "88") (name "Net-(B4-LV_TXI_2)") (class "Default")
      (node (ref "B4") (pin "LV4") (pinfunction "LV_TXI_2_LV4") (pintype "bidirectional"))
      (node (ref "U$2") (pin "10/CS") (pinfunction "10/CS_10/CS") (pintype "bidirectional"))
    )
    (net (code "89") (name "Net-(IC1D-I0)") (class "Default")
      (node (ref "IC1") (pin "12") (pinfunction "I0_12") (pintype "input"))
      (node (ref "IC1") (pin "13") (pinfunction "I1_13") (pintype "input"))
      (node (ref "U$1") (pin "P$15") (pinfunction "RD*_P$15") (pintype "bidirectional"))
    )
    (net (code "90") (name "Net-(IC3A-I0)") (class "Default")
      (node (ref "IC3") (pin "1") (pinfunction "I0_1") (pintype "input"))
      (node (ref "U$1") (pin "P$35") (pinfunction "A5_P$35") (pintype "bidirectional"))
    )
    (net (code "91") (name "Net-(IC3A-I1)") (class "Default")
      (node (ref "IC3") (pin "2") (pinfunction "I1_2") (pintype "input"))
      (node (ref "U$1") (pin "P$38") (pinfunction "A6_P$38") (pintype "bidirectional"))
    )
    (net (code "92") (name "Net-(IC3A-I2)") (class "Default")
      (node (ref "IC3") (pin "3") (pinfunction "I2_3") (pintype "input"))
      (node (ref "U$1") (pin "P$36") (pinfunction "A7_P$36") (pintype "bidirectional"))
    )
    (net (code "93") (name "Net-(IC3A-I3)") (class "Default")
      (node (ref "IC3") (pin "4") (pinfunction "I3_4") (pintype "input"))
      (node (ref "U$1") (pin "P$11") (pinfunction "A8_P$11") (pintype "bidirectional"))
    )
    (net (code "94") (name "Net-(IC3A-I4)") (class "Default")
      (node (ref "IC3") (pin "5") (pinfunction "I4_5") (pintype "input"))
      (node (ref "U$1") (pin "P$17") (pinfunction "A9_P$17") (pintype "bidirectional"))
    )
    (net (code "95") (name "Net-(IC3A-I5)") (class "Default")
      (node (ref "IC3") (pin "6") (pinfunction "I5_6") (pintype "input"))
      (node (ref "U$1") (pin "P$4") (pinfunction "A10_P$4") (pintype "bidirectional"))
    )
    (net (code "96") (name "Net-(IC3A-I6)") (class "Default")
      (node (ref "IC3") (pin "11") (pinfunction "I6_11") (pintype "input"))
      (node (ref "U$1") (pin "P$5") (pinfunction "A12_P$5") (pintype "bidirectional"))
    )
    (net (code "97") (name "Net-(IC3A-I7)") (class "Default")
      (node (ref "IC3") (pin "12") (pinfunction "I7_12") (pintype "input"))
      (node (ref "U$1") (pin "P$6") (pinfunction "A13_P$6") (pintype "bidirectional"))
    )
    (net (code "98") (name "Net-(IC6A-A)") (class "Default")
      (node (ref "IC6") (pin "2") (pinfunction "A_2") (pintype "input"))
      (node (ref "U$1") (pin "P$10") (pinfunction "A14_P$10") (pintype "bidirectional"))
    )
    (net (code "99") (name "Net-(IC6A-B)") (class "Default")
      (node (ref "IC6") (pin "3") (pinfunction "B_3") (pintype "input"))
      (node (ref "U$1") (pin "P$7") (pinfunction "A15_P$7") (pintype "bidirectional"))
    )
    (net (code "100") (name "Net-(IC6A-G)") (class "Default")
      (node (ref "IC6") (pin "1") (pinfunction "G_1") (pintype "input"))
      (node (ref "U$1") (pin "P$1") (pinfunction "RAS*_P$1") (pintype "bidirectional"))
    )
    (net (code "101") (name "Net-(IC6B-B)") (class "Default")
      (node (ref "IC6") (pin "13") (pinfunction "B_13") (pintype "input"))
      (node (ref "U$1") (pin "P$9") (pinfunction "A11_P$9") (pintype "bidirectional"))
    )
    (net (code "102") (name "Net-(IC7A-2C)") (class "Default")
      (node (ref "IC7") (pin "15") (pinfunction "2C_15") (pintype "input"))
      (node (ref "U$1") (pin "P$13") (pinfunction "WR*_P$13") (pintype "bidirectional"))
    )
    (net (code "103") (name "Net-(IC7A-A)") (class "Default")
      (node (ref "IC7") (pin "13") (pinfunction "A_13") (pintype "input"))
      (node (ref "U$1") (pin "P$40") (pinfunction "A2_P$40") (pintype "bidirectional"))
    )
    (net (code "104") (name "Net-(IC7A-B)") (class "Default")
      (node (ref "IC7") (pin "3") (pinfunction "B_3") (pintype "input"))
      (node (ref "U$1") (pin "P$34") (pinfunction "A3_P$34") (pintype "bidirectional"))
    )
    (net (code "105") (name "Net-(IC9-VI)") (class "Default")
      (node (ref "C9") (pin "+") (pinfunction "+_+") (pintype "passive"))
      (node (ref "IC9") (pin "1") (pinfunction "VI_1") (pintype "input"))
      (node (ref "S1") (pin "3") (pinfunction "S_3") (pintype "passive"))
    )
    (net (code "106") (name "Net-(R1-Pad1)") (class "Default")
      (node (ref "R1") (pin "1") (pinfunction "1_1") (pintype "passive"))
      (node (ref "U$2") (pin "7") (pinfunction "7_7") (pintype "bidirectional"))
    )
    (net (code "107") (name "Net-(R2-Pad1)") (class "Default")
      (node (ref "R2") (pin "1") (pinfunction "1_1") (pintype "passive"))
      (node (ref "U$2") (pin "6") (pinfunction "6_6") (pintype "bidirectional"))
    )
    (net (code "108") (name "Net-(R3-Pad1)") (class "Default")
      (node (ref "R3") (pin "1") (pinfunction "1_1") (pintype "passive"))
      (node (ref "U$2") (pin "5") (pinfunction "5_5") (pintype "bidirectional"))
    )
    (net (code "109") (name "Net-(R4-Pad1)") (class "Default")
      (node (ref "R4") (pin "1") (pinfunction "1_1") (pintype "passive"))
      (node (ref "U$2") (pin "4/CANRX") (pinfunction "4/CANRX_4/CANRX") (pintype "bidirectional"))
    )
    (net (code "110") (name "Net-(R5-Pad1)") (class "Default")
      (node (ref "R5") (pin "1") (pinfunction "1_1") (pintype "passive"))
      (node (ref "U$2") (pin "3/CANTX") (pinfunction "3/CANTX_3/CANTX") (pintype "bidirectional"))
    )
    (net (code "111") (name "Net-(R6-Pad1)") (class "Default")
      (node (ref "R6") (pin "1") (pinfunction "1_1") (pintype "passive"))
      (node (ref "U$2") (pin "2") (pinfunction "2_2") (pintype "bidirectional"))
    )
    (net (code "112") (name "Net-(RGB_LED1-BLUE)") (class "Default")
      (node (ref "R1") (pin "2") (pinfunction "2_2") (pintype "passive"))
      (node (ref "RGB_LED1") (pin "1") (pinfunction "BLUE_1") (pintype "bidirectional"))
    )
    (net (code "113") (name "Net-(RGB_LED1-GREEN)") (class "Default")
      (node (ref "R2") (pin "2") (pinfunction "2_2") (pintype "passive"))
      (node (ref "RGB_LED1") (pin "2") (pinfunction "GREEN_2") (pintype "bidirectional"))
    )
    (net (code "114") (name "Net-(RGB_LED1-RED)") (class "Default")
      (node (ref "R3") (pin "2") (pinfunction "2_2") (pintype "passive"))
      (node (ref "RGB_LED1") (pin "4") (pinfunction "RED_4") (pintype "bidirectional"))
    )
    (net (code "115") (name "Net-(RGB_LED2-BLUE)") (class "Default")
      (node (ref "R4") (pin "2") (pinfunction "2_2") (pintype "passive"))
      (node (ref "RGB_LED2") (pin "1") (pinfunction "BLUE_1") (pintype "bidirectional"))
    )
    (net (code "116") (name "Net-(RGB_LED2-GREEN)") (class "Default")
      (node (ref "R5") (pin "2") (pinfunction "2_2") (pintype "passive"))
      (node (ref "RGB_LED2") (pin "2") (pinfunction "GREEN_2") (pintype "bidirectional"))
    )
    (net (code "117") (name "Net-(RGB_LED2-RED)") (class "Default")
      (node (ref "R6") (pin "2") (pinfunction "2_2") (pintype "passive"))
      (node (ref "RGB_LED2") (pin "4") (pinfunction "RED_4") (pintype "bidirectional"))
    )
    (net (code "118") (name "Net-(S1-P)") (class "Default")
      (node (ref "J1") (pin "3") (pinfunction "3_3") (pintype "passive"))
      (node (ref "S1") (pin "2") (pinfunction "P_2") (pintype "passive"))
    )
    (net (code "119") (name "Net-(U$2-Pad3V3_LO)") (class "Default")
      (node (ref "U$2") (pin "3V3_LO") (pinfunction "3V3_LO_3V3_LO") (pintype "bidirectional"))
      (node (ref "U$2") (pin "AREF") (pinfunction "AREF_AREF") (pintype "bidirectional"))
    )
    (net (code "120") (name "VCC") (class "Default")
      (node (ref "B1") (pin "HV") (pinfunction "HV_HV") (pintype "power_in"))
      (node (ref "B2") (pin "HV") (pinfunction "HV_HV") (pintype "power_in"))
      (node (ref "B3") (pin "HV") (pinfunction "HV_HV") (pintype "power_in"))
      (node (ref "B4") (pin "HV") (pinfunction "HV_HV") (pintype "power_in"))
      (node (ref "B5") (pin "HV") (pinfunction "HV_HV") (pintype "power_in"))
      (node (ref "B6") (pin "HV") (pinfunction "HV_HV") (pintype "power_in"))
      (node (ref "C1") (pin "2") (pinfunction "2_2") (pintype "passive"))
      (node (ref "C10") (pin "+") (pinfunction "+_+") (pintype "passive"))
      (node (ref "C11") (pin "1") (pinfunction "1_1") (pintype "passive"))
      (node (ref "C2") (pin "2") (pinfunction "2_2") (pintype "passive"))
      (node (ref "C3") (pin "2") (pinfunction "2_2") (pintype "passive"))
      (node (ref "C4") (pin "2") (pinfunction "2_2") (pintype "passive"))
      (node (ref "C5") (pin "2") (pinfunction "2_2") (pintype "passive"))
      (node (ref "C6") (pin "2") (pinfunction "2_2") (pintype "passive"))
      (node (ref "C7") (pin "2") (pinfunction "2_2") (pintype "passive"))
      (node (ref "C8") (pin "2") (pinfunction "2_2") (pintype "passive"))
      (node (ref "IC1") (pin "14") (pinfunction "VCC_14") (pintype "power_in"))
      (node (ref "IC11") (pin "14") (pinfunction "VCC_14") (pintype "power_in"))
      (node (ref "IC2") (pin "20") (pinfunction "VCC_20") (pintype "power_in"))
      (node (ref "IC3") (pin "14") (pinfunction "VCC_14") (pintype "power_in"))
      (node (ref "IC4") (pin "20") (pinfunction "VCC_20") (pintype "power_in"))
      (node (ref "IC5") (pin "14") (pinfunction "VCC_14") (pintype "power_in"))
      (node (ref "IC5") (pin "2") (pinfunction "D_2") (pintype "input"))
      (node (ref "IC6") (pin "16") (pinfunction "VCC_16") (pintype "power_in"))
      (node (ref "IC7") (pin "16") (pinfunction "VCC_16") (pintype "power_in"))
      (node (ref "IC9") (pin "3") (pinfunction "VO_3") (pintype "passive"))
      (node (ref "J2") (pin "2") (pinfunction "2_2") (pintype "passive"))
      (node (ref "J3") (pin "2") (pinfunction "2_2") (pintype "passive"))
      (node (ref "R7") (pin "1") (pinfunction "1_1") (pintype "passive"))
      (node (ref "U$2") (pin "VIN") (pinfunction "VIN_VIN") (pintype "bidirectional"))
    )
    (net (code "121") (name "VCC{slash}2") (class "Default")
      (node (ref "B1") (pin "LV") (pinfunction "LV_LV") (pintype "power_in"))
      (node (ref "B2") (pin "LV") (pinfunction "LV_LV") (pintype "power_in"))
      (node (ref "B3") (pin "LV") (pinfunction "LV_LV") (pintype "power_in"))
      (node (ref "B4") (pin "LV") (pinfunction "LV_LV") (pintype "power_in"))
      (node (ref "B5") (pin "LV") (pinfunction "LV_LV") (pintype "power_in"))
      (node (ref "B6") (pin "LV") (pinfunction "LV_LV") (pintype "power_in"))
      (node (ref "U$2") (pin "3V3_2") (pinfunction "3V3_2_3V3_2") (pintype "bidirectional"))
    )
    (net (code "122") (name "unconnected-(IC5A-Q-Pad5)") (class "Default")
      (node (ref "IC5") (pin "5") (pinfunction "Q_5") (pintype "output"))
    )
    (net (code "123") (name "unconnected-(IC5B-Q-Pad9)") (class "Default")
      (node (ref "IC5") (pin "9") (pinfunction "Q_9") (pintype "output"))
    )
    (net (code "124") (name "unconnected-(IC5B-~{Q}-Pad8)") (class "Default")
      (node (ref "IC5") (pin "8") (pinfunction "~{Q}_8") (pintype "output"))
    )
    (net (code "125") (name "unconnected-(IC6A-Y1-Pad5)") (class "Default")
      (node (ref "IC6") (pin "5") (pinfunction "Y1_5") (pintype "output"))
    )
    (net (code "126") (name "unconnected-(IC6A-Y2-Pad6)") (class "Default")
      (node (ref "IC6") (pin "6") (pinfunction "Y2_6") (pintype "output"))
    )
    (net (code "127") (name "unconnected-(IC6A-Y3-Pad7)") (class "Default")
      (node (ref "IC6") (pin "7") (pinfunction "Y3_7") (pintype "output"))
    )
    (net (code "128") (name "unconnected-(IC6B-Y1-Pad11)") (class "Default")
      (node (ref "IC6") (pin "11") (pinfunction "Y1_11") (pintype "output"))
    )
    (net (code "129") (name "unconnected-(IC6B-Y2-Pad10)") (class "Default")
      (node (ref "IC6") (pin "10") (pinfunction "Y2_10") (pintype "output"))
    )
    (net (code "130") (name "unconnected-(IC6B-Y3-Pad9)") (class "Default")
      (node (ref "IC6") (pin "9") (pinfunction "Y3_9") (pintype "output"))
    )
    (net (code "131") (name "unconnected-(J3-Pad4)") (class "Default")
      (node (ref "J3") (pin "4") (pinfunction "4_4") (pintype "passive"))
    )
    (net (code "132") (name "unconnected-(J3-Pad6)") (class "Default")
      (node (ref "J3") (pin "6") (pinfunction "6_6") (pintype "passive"))
    )
    (net (code "133") (name "unconnected-(J3-Pad8)") (class "Default")
      (node (ref "J3") (pin "8") (pinfunction "8_8") (pintype "passive"))
    )
    (net (code "134") (name "unconnected-(S1-O-Pad1)") (class "Default")
      (node (ref "S1") (pin "1") (pinfunction "O_1") (pintype "passive"))
    )
    (net (code "135") (name "unconnected-(U$1-A4-PadP$31)") (class "Default")
      (node (ref "U$1") (pin "P$31") (pinfunction "A4_P$31") (pintype "bidirectional"))
    )
    (net (code "136") (name "unconnected-(U$1-CAS*-PadP$3)") (class "Default")
      (node (ref "U$1") (pin "P$3") (pinfunction "CAS*_P$3") (pintype "bidirectional"))
    )
    (net (code "137") (name "unconnected-(U$1-IN*-PadP$19)") (class "Default")
      (node (ref "U$1") (pin "P$19") (pinfunction "IN*_P$19") (pintype "bidirectional"))
    )
    (net (code "138") (name "unconnected-(U$1-INTAK*-PadP$14)") (class "Default")
      (node (ref "U$1") (pin "P$14") (pinfunction "INTAK*_P$14") (pintype "bidirectional"))
    )
    (net (code "139") (name "unconnected-(U$1-MUX-PadP$16)") (class "Default")
      (node (ref "U$1") (pin "P$16") (pinfunction "MUX_P$16") (pintype "bidirectional"))
    )
    (net (code "140") (name "unconnected-(U$1-NC-PadP$39)") (class "Default")
      (node (ref "U$1") (pin "P$39") (pinfunction "NC_P$39") (pintype "bidirectional"))
    )
    (net (code "141") (name "unconnected-(U$1-OUT*-PadP$12)") (class "Default")
      (node (ref "U$1") (pin "P$12") (pinfunction "OUT*_P$12") (pintype "bidirectional"))
    )
    (net (code "142") (name "unconnected-(U$1-SYSRES*-PadP$2)") (class "Default")
      (node (ref "U$1") (pin "P$2") (pinfunction "SYSRES*_P$2") (pintype "bidirectional"))
    )
    (net (code "143") (name "unconnected-(U$1-TEST*-PadP$23)") (class "Default")
      (node (ref "U$1") (pin "P$23") (pinfunction "TEST*_P$23") (pintype "bidirectional"))
    )
    (net (code "144") (name "unconnected-(U$2-A21{slash}DAC0-Pad21{slash}DAC0)") (class "Default")
      (node (ref "U$2") (pin "21/DAC0") (pinfunction "A21/DAC0_21/DAC0") (pintype "bidirectional"))
    )
    (net (code "145") (name "unconnected-(U$2-Pad0{slash}RX)") (class "Default")
      (node (ref "U$2") (pin "0/RX") (pinfunction "0/RX_0/RX") (pintype "bidirectional"))
    )
    (net (code "146") (name "unconnected-(U$2-Pad1{slash}TX)") (class "Default")
      (node (ref "U$2") (pin "1/TX") (pinfunction "1/TX_1/TX") (pintype "bidirectional"))
    )
    (net (code "147") (name "unconnected-(U$2-Pad3V3)") (class "Default")
      (node (ref "U$2") (pin "3V3") (pinfunction "3V3_3V3") (pintype "bidirectional"))
    )
    (net (code "148") (name "unconnected-(U$2-Pad14{slash}A0)") (class "Default")
      (node (ref "U$2") (pin "14/A0") (pinfunction "14/A0_14/A0") (pintype "bidirectional"))
    )
    (net (code "149") (name "unconnected-(U$2-Pad16{slash}A2)") (class "Default")
      (node (ref "U$2") (pin "16/A2") (pinfunction "16/A2_16/A2") (pintype "bidirectional"))
    )
    (net (code "150") (name "unconnected-(U$2-Pad17{slash}A3)") (class "Default")
      (node (ref "U$2") (pin "17/A3") (pinfunction "17/A3_17/A3") (pintype "bidirectional"))
    )
    (net (code "151") (name "unconnected-(U$2-Pad18{slash}A4{slash}SDA)") (class "Default")
      (node (ref "U$2") (pin "18/A4/SDA") (pinfunction "18/A4/SDA_18/A4/SDA") (pintype "bidirectional"))
    )
    (net (code "152") (name "unconnected-(U$2-Pad19{slash}A5{slash}SCL)") (class "Default")
      (node (ref "U$2") (pin "19/A5/SCL") (pinfunction "19/A5/SCL_19/A5/SCL") (pintype "bidirectional"))
    )
    (net (code "153") (name "unconnected-(U$2-Pad20{slash}A6)") (class "Default")
      (node (ref "U$2") (pin "20/A6") (pinfunction "20/A6_20/A6") (pintype "bidirectional"))
    )
    (net (code "154") (name "unconnected-(U$2-Pad21{slash}A7)") (class "Default")
      (node (ref "U$2") (pin "21/A7") (pinfunction "21/A7_21/A7") (pintype "bidirectional"))
    )
    (net (code "155") (name "unconnected-(U$2-Pad24)") (class "Default")
      (node (ref "U$2") (pin "24") (pinfunction "24_24") (pintype "bidirectional"))
    )
    (net (code "156") (name "unconnected-(U$2-PadA10)") (class "Default")
      (node (ref "U$2") (pin "A10") (pinfunction "A10_A10") (pintype "bidirectional"))
    )
    (net (code "157") (name "unconnected-(U$2-PadA11)") (class "Default")
      (node (ref "U$2") (pin "A11") (pinfunction "A11_A11") (pintype "bidirectional"))
    )
    (net (code "158") (name "unconnected-(U$2-PadA22{slash}DAC1)") (class "Default")
      (node (ref "U$2") (pin "A22/DAC1") (pinfunction "A22/DAC1_A22/DAC1") (pintype "bidirectional"))
    )
    (net (code "159") (name "unconnected-(U$2-PadPROG)") (class "Default")
      (node (ref "U$2") (pin "PROG") (pinfunction "PROG_PROG") (pintype "bidirectional"))
    )
    (net (code "160") (name "unconnected-(U$2-PadRESET)") (class "Default")
      (node (ref "U$2") (pin "RESET") (pinfunction "RESET_RESET") (pintype "bidirectional"))
    )
    (net (code "161") (name "unconnected-(U$2-PadU5V)") (class "Default")
      (node (ref "U$2") (pin "U5V") (pinfunction "U5V_U5V") (pintype "bidirectional"))
    )
    (net (code "162") (name "unconnected-(U$2-PadUD+)") (class "Default")
      (node (ref "U$2") (pin "UD+") (pinfunction "UD+_UD+") (pintype "bidirectional"))
    )
    (net (code "163") (name "unconnected-(U$2-PadUD-)") (class "Default")
      (node (ref "U$2") (pin "UD-") (pinfunction "UD-_UD-") (pintype "bidirectional"))
    )
    (net (code "164") (name "unconnected-(U$2-PadVBAT)") (class "Default")
      (node (ref "U$2") (pin "VBAT") (pinfunction "VBAT_VBAT") (pintype "bidirectional"))
    )
    (net (code "165") (name "unconnected-(U$2-PadVUSB)") (class "Default")
      (node (ref "U$2") (pin "VUSB") (pinfunction "VUSB_VUSB") (pintype "bidirectional"))
    )
  )
)
